# adapter.net
KiCad netlist of a schematic drawn in EAGLE
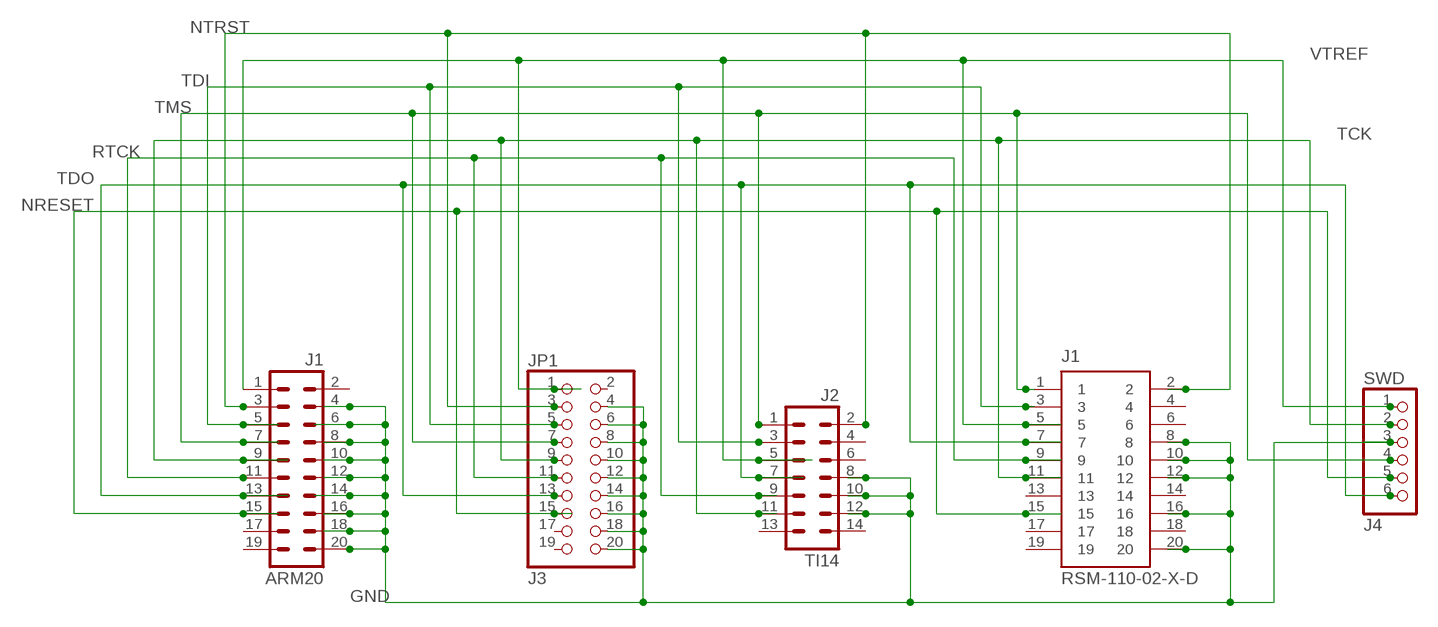
[diagram p0: schematic, sheet 1]

(export (version "E")
  (design (tool "Eeschema 10.0.6"))
  (components
    (comp (ref "ARM20")
      (value "J1")
      (footprint "eagle-import:ML20")
      (libsource (lib "eagle-import") (part "ML20"))
    )
    (comp (ref "J1")
      (value "RSM-110-02-X-D")
      (footprint "eagle-import:RSM-110-02-X-D")
      (libsource (lib "eagle-import") (part "RSM-110-02-X-D"))
    )
    (comp (ref "JP1")
      (value "J3")
      (footprint "eagle-import:2X10")
      (libsource (lib "eagle-import") (part "PINHD-2X10"))
    )
    (comp (ref "SWD")
      (value "J4")
      (footprint "eagle-import:1X06")
      (libsource (lib "eagle-import") (part "PINHD-1X6"))
    )
    (comp (ref "TI14")
      (value "J2")
      (footprint "eagle-import:ML14")
      (libsource (lib "eagle-import") (part "ML14"))
    )
  )
  (nets
    (net (code "1") (name "/GND") (class "Default")
      (node (ref "ARM20") (pin "10") (pinfunction "10_10") (pintype "passive"))
      (node (ref "ARM20") (pin "12") (pinfunction "12_12") (pintype "passive"))
      (node (ref "ARM20") (pin "14") (pinfunction "14_14") (pintype "passive"))
      (node (ref "ARM20") (pin "16") (pinfunction "16_16") (pintype "passive"))
      (node (ref "ARM20") (pin "18") (pinfunction "18_18") (pintype "passive"))
      (node (ref "ARM20") (pin "20") (pinfunction "20_20") (pintype "passive"))
      (node (ref "ARM20") (pin "4") (pinfunction "4_4") (pintype "passive"))
      (node (ref "ARM20") (pin "6") (pinfunction "6_6") (pintype "passive"))
      (node (ref "ARM20") (pin "8") (pinfunction "8_8") (pintype "passive"))
      (node (ref "J1") (pin "10") (pinfunction "10_10") (pintype "bidirectional"))
      (node (ref "J1") (pin "12") (pinfunction "12_12") (pintype "bidirectional"))
      (node (ref "J1") (pin "16") (pinfunction "16_16") (pintype "bidirectional"))
      (node (ref "J1") (pin "20") (pinfunction "20_20") (pintype "bidirectional"))
      (node (ref "J1") (pin "8") (pinfunction "8_8") (pintype "bidirectional"))
      (node (ref "JP1") (pin "10") (pinfunction "10_10") (pintype "passive"))
      (node (ref "JP1") (pin "12") (pinfunction "12_12") (pintype "passive"))
      (node (ref "JP1") (pin "14") (pinfunction "14_14") (pintype "passive"))
      (node (ref "JP1") (pin "16") (pinfunction "16_16") (pintype "passive"))
      (node (ref "JP1") (pin "18") (pinfunction "18_18") (pintype "passive"))
      (node (ref "JP1") (pin "20") (pinfunction "20_20") (pintype "passive"))
      (node (ref "JP1") (pin "4") (pinfunction "4_4") (pintype "passive"))
      (node (ref "JP1") (pin "6") (pinfunction "6_6") (pintype "passive"))
      (node (ref "JP1") (pin "8") (pinfunction "8_8") (pintype "passive"))
      (node (ref "SWD") (pin "3") (pinfunction "3_3") (pintype "passive"))
      (node (ref "TI14") (pin "10") (pinfunction "10_10") (pintype "passive"))
      (node (ref "TI14") (pin "12") (pinfunction "12_12") (pintype "passive"))
      (node (ref "TI14") (pin "8") (pinfunction "8_8") (pintype "passive"))
    )
    (net (code "2") (name "/NRESET") (class "Default")
      (node (ref "ARM20") (pin "15") (pinfunction "15_15") (pintype "passive"))
      (node (ref "J1") (pin "15") (pinfunction "15_15") (pintype "bidirectional"))
      (node (ref "JP1") (pin "15") (pinfunction "15_15") (pintype "passive"))
      (node (ref "SWD") (pin "5") (pinfunction "5_5") (pintype "passive"))
    )
    (net (code "3") (name "/NTRST") (class "Default")
      (node (ref "ARM20") (pin "3") (pinfunction "3_3") (pintype "passive"))
      (node (ref "J1") (pin "2") (pinfunction "2_2") (pintype "bidirectional"))
      (node (ref "JP1") (pin "3") (pinfunction "3_3") (pintype "passive"))
      (node (ref "TI14") (pin "2") (pinfunction "2_2") (pintype "passive"))
    )
    (net (code "4") (name "/RTCK") (class "Default")
      (node (ref "ARM20") (pin "11") (pinfunction "11_11") (pintype "passive"))
      (node (ref "J1") (pin "9") (pinfunction "9_9") (pintype "bidirectional"))
      (node (ref "JP1") (pin "11") (pinfunction "11_11") (pintype "passive"))
      (node (ref "TI14") (pin "9") (pinfunction "9_9") (pintype "passive"))
    )
    (net (code "5") (name "/TCK") (class "Default")
      (node (ref "ARM20") (pin "9") (pinfunction "9_9") (pintype "passive"))
      (node (ref "J1") (pin "11") (pinfunction "11_11") (pintype "bidirectional"))
      (node (ref "JP1") (pin "9") (pinfunction "9_9") (pintype "passive"))
      (node (ref "SWD") (pin "2") (pinfunction "2_2") (pintype "passive"))
      (node (ref "TI14") (pin "11") (pinfunction "11_11") (pintype "passive"))
    )
    (net (code "6") (name "/TDI") (class "Default")
      (node (ref "ARM20") (pin "5") (pinfunction "5_5") (pintype "passive"))
      (node (ref "J1") (pin "3") (pinfunction "3_3") (pintype "bidirectional"))
      (node (ref "JP1") (pin "5") (pinfunction "5_5") (pintype "passive"))
      (node (ref "TI14") (pin "3") (pinfunction "3_3") (pintype "passive"))
    )
    (net (code "7") (name "/TDO") (class "Default")
      (node (ref "ARM20") (pin "13") (pinfunction "13_13") (pintype "passive"))
      (node (ref "J1") (pin "7") (pinfunction "7_7") (pintype "bidirectional"))
      (node (ref "JP1") (pin "13") (pinfunction "13_13") (pintype "passive"))
      (node (ref "SWD") (pin "6") (pinfunction "6_6") (pintype "passive"))
      (node (ref "TI14") (pin "7") (pinfunction "7_7") (pintype "passive"))
    )
    (net (code "8") (name "/TMS") (class "Default")
      (node (ref "ARM20") (pin "7") (pinfunction "7_7") (pintype "passive"))
      (node (ref "J1") (pin "1") (pinfunction "1_1") (pintype "bidirectional"))
      (node (ref "JP1") (pin "7") (pinfunction "7_7") (pintype "passive"))
      (node (ref "SWD") (pin "4") (pinfunction "4_4") (pintype "passive"))
      (node (ref "TI14") (pin "1") (pinfunction "1_1") (pintype "passive"))
    )
    (net (code "9") (name "/VTREF") (class "Default")
      (node (ref "ARM20") (pin "1") (pinfunction "1_1") (pintype "passive"))
      (node (ref "J1") (pin "5") (pinfunction "5_5") (pintype "bidirectional"))
      (node (ref "JP1") (pin "1") (pinfunction "1_1") (pintype "passive"))
      (node (ref "SWD") (pin "1") (pinfunction "1_1") (pintype "passive"))
      (node (ref "TI14") (pin "5") (pinfunction "5_5") (pintype "passive"))
    )
    (net (code "10") (name "unconnected-(ARM20-Pad2)") (class "Default")
      (node (ref "ARM20") (pin "2") (pinfunction "2_2") (pintype "passive"))
    )
    (net (code "11") (name "unconnected-(ARM20-Pad17)") (class "Default")
      (node (ref "ARM20") (pin "17") (pinfunction "17_17") (pintype "passive"))
    )
    (net (code "12") (name "unconnected-(ARM20-Pad19)") (class "Default")
      (node (ref "ARM20") (pin "19") (pinfunction "19_19") (pintype "passive"))
    )
    (net (code "13") (name "unconnected-(J1-Pad4)") (class "Default")
      (node (ref "J1") (pin "4") (pinfunction "4_4") (pintype "bidirectional"))
    )
    (net (code "14") (name "unconnected-(J1-Pad6)") (class "Default")
      (node (ref "J1") (pin "6") (pinfunction "6_6") (pintype "bidirectional"))
    )
    (net (code "15") (name "unconnected-(J1-Pad13)") (class "Default")
      (node (ref "J1") (pin "13") (pinfunction "13_13") (pintype "bidirectional"))
    )
    (net (code "16") (name "unconnected-(J1-Pad14)") (class "Default")
      (node (ref "J1") (pin "14") (pinfunction "14_14") (pintype "bidirectional"))
    )
    (net (code "17") (name "unconnected-(J1-Pad17)") (class "Default")
      (node (ref "J1") (pin "17") (pinfunction "17_17") (pintype "bidirectional"))
    )
    (net (code "18") (name "unconnected-(J1-Pad18)") (class "Default")
      (node (ref "J1") (pin "18") (pinfunction "18_18") (pintype "bidirectional"))
    )
    (net (code "19") (name "unconnected-(J1-Pad19)") (class "Default")
      (node (ref "J1") (pin "19") (pinfunction "19_19") (pintype "bidirectional"))
    )
    (net (code "20") (name "unconnected-(JP1-Pad2)") (class "Default")
      (node (ref "JP1") (pin "2") (pinfunction "2_2") (pintype "passive"))
    )
    (net (code "21") (name "unconnected-(JP1-Pad17)") (class "Default")
      (node (ref "JP1") (pin "17") (pinfunction "17_17") (pintype "passive"))
    )
    (net (code "22") (name "unconnected-(JP1-Pad19)") (class "Default")
      (node (ref "JP1") (pin "19") (pinfunction "19_19") (pintype "passive"))
    )
    (net (code "23") (name "unconnected-(TI14-Pad4)") (class "Default")
      (node (ref "TI14") (pin "4") (pinfunction "4_4") (pintype "passive"))
    )
    (net (code "24") (name "unconnected-(TI14-Pad6)") (class "Default")
      (node (ref "TI14") (pin "6") (pinfunction "6_6") (pintype "passive"))
    )
    (net (code "25") (name "unconnected-(TI14-Pad13)") (class "Default")
      (node (ref "TI14") (pin "13") (pinfunction "13_13") (pintype "passive"))
    )
    (net (code "26") (name "unconnected-(TI14-Pad14)") (class "Default")
      (node (ref "TI14") (pin "14") (pinfunction "14_14") (pintype "passive"))
    )
  )
)
